# IRKitESP8266_v11.net
KiCad netlist of a schematic drawn in EAGLE
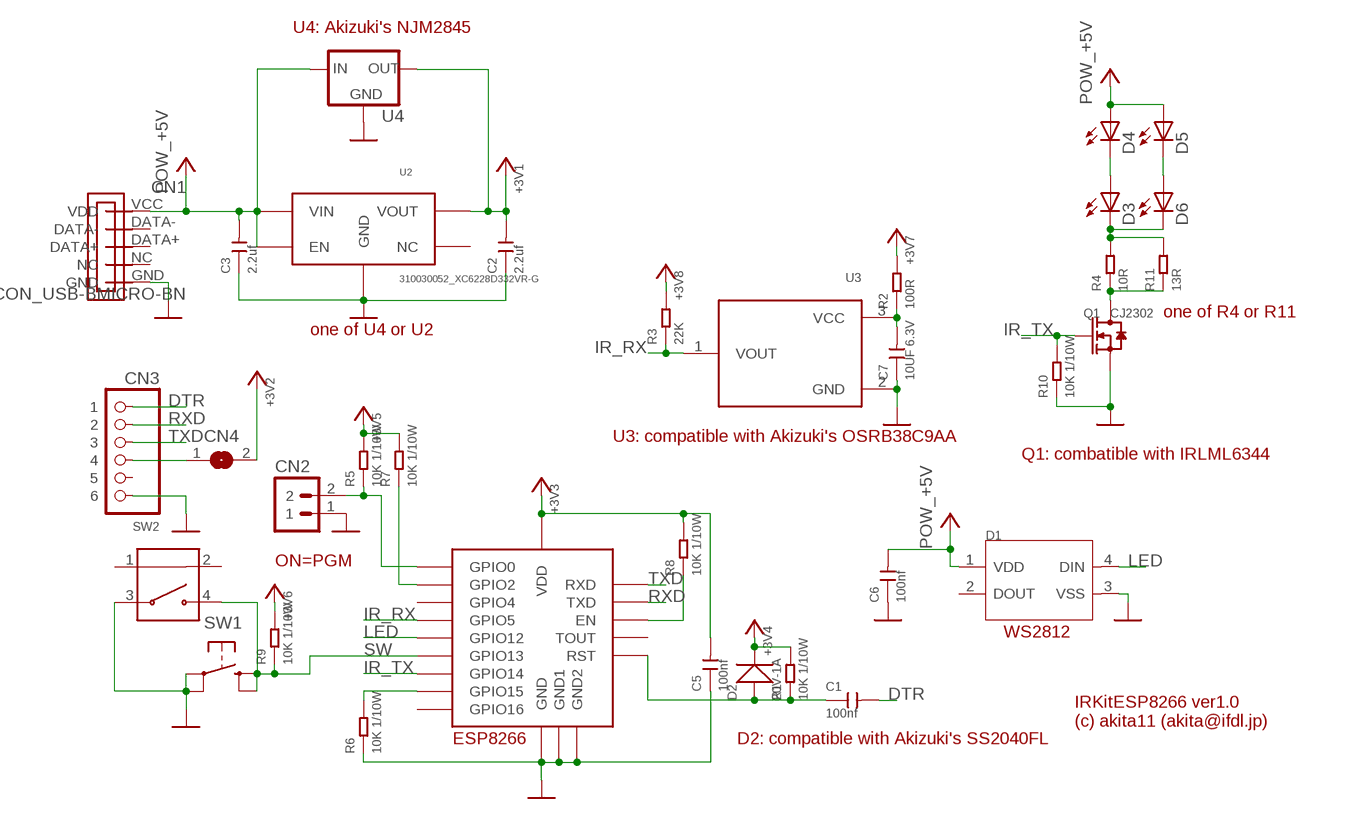
[diagram p0: schematic, sheet 1]

(export (version "E")
  (design (tool "Eeschema 10.0.6"))
  (components
    (comp (ref "C1")
      (value "100nf")
      (footprint "eagle-import:C0603")
      (fields (field (name "MPN") "CC0603KRX7R9BB104"))
      (libsource (lib "eagle-import") (part "CERAMIC-100NF-50V-10%-X7R(0603)"))
    )
    (comp (ref "C2")
      (value "2.2uf")
      (footprint "eagle-import:C0603")
      (fields (field (name "MPN") "CC0603KRX7R6BB225"))
      (libsource (lib "eagle-import") (part "CERAMIC-2.2UF-10V-10%-X7R(0603)"))
    )
    (comp (ref "C3")
      (value "2.2uf")
      (footprint "eagle-import:C0603")
      (fields (field (name "MPN") "CC0603KRX7R6BB225"))
      (libsource (lib "eagle-import") (part "CERAMIC-2.2UF-10V-10%-X7R(0603)"))
    )
    (comp (ref "C5")
      (value "100nf")
      (footprint "eagle-import:C0603")
      (fields (field (name "MPN") "CC0603KRX7R9BB104"))
      (libsource (lib "eagle-import") (part "CERAMIC-100NF-50V-10%-X7R(0603)"))
    )
    (comp (ref "C6")
      (value "100nf")
      (footprint "eagle-import:C0603")
      (fields (field (name "MPN") "CC0603KRX7R9BB104"))
      (libsource (lib "eagle-import") (part "CERAMIC-100NF-50V-10%-X7R(0603)"))
    )
    (comp (ref "C7")
      (value "10UF 6.3V")
      (footprint "eagle-import:C0603")
      (fields (field (name "MPN") "CC0603MRX5R5BB106"))
      (libsource (lib "eagle-import") (part "CERAMIC-10UF-6.3V-20%-X5R(0603)"))
    )
    (comp (ref "CN1")
      (value "CON_USB-BMICRO-BN")
      (footprint "eagle-import:MICRO-USB_B_NARROW")
      (libsource (lib "eagle-import") (part "CON_USB-BMICRO-BN"))
    )
    (comp (ref "CN2")
      (value "CON_PINHD-1X2PTH")
      (footprint "eagle-import:SPARKFUN_1X02")
      (libsource (lib "eagle-import") (part "CON_PINHD-1X2PTH"))
    )
    (comp (ref "CN3")
      (value "CON_PINHD-1X6")
      (footprint "eagle-import:1X06")
      (libsource (lib "eagle-import") (part "CON_PINHD-1X6"))
    )
    (comp (ref "CN4")
      (value "JUMPER_SJ")
      (footprint "eagle-import:JUMPER_SJ")
      (libsource (lib "eagle-import") (part "JUMPER_SJ"))
    )
    (comp (ref "D1")
      (value "SMD-RGB-LED-4P'WS2812B'")
      (footprint "eagle-import:LED4-SMD-5050")
      (libsource (lib "eagle-import") (part "SMD-RGB-LED-4P'WS2812B'"))
    )
    (comp (ref "D2")
      (value "20V-1A")
      (footprint "eagle-import:SOD-123")
      (fields (field (name "MPN") "B5819W"))
      (libsource (lib "eagle-import") (part "SMD-DIODE-SCHOTTKY-20V-1A(SOD-123)"))
    )
    (comp (ref "D3")
      (value "LED5MM")
      (footprint "eagle-import:SPARKFUN_LED5MM")
      (libsource (lib "eagle-import") (part "LED5MM"))
    )
    (comp (ref "D4")
      (value "LED5MM")
      (footprint "eagle-import:SPARKFUN_LED5MM")
      (libsource (lib "eagle-import") (part "LED5MM"))
    )
    (comp (ref "D5")
      (value "LED5MM")
      (footprint "eagle-import:SPARKFUN_LED5MM")
      (libsource (lib "eagle-import") (part "LED5MM"))
    )
    (comp (ref "D6")
      (value "LED5MM")
      (footprint "eagle-import:SPARKFUN_LED5MM")
      (libsource (lib "eagle-import") (part "LED5MM"))
    )
    (comp (ref "Q1")
      (value "CJ2302")
      (footprint "eagle-import:SOT-23")
      (libsource (lib "eagle-import") (part "SMD-MOSFET-N-CH-20V-2.1A-CJ2302(SOT-23)"))
    )
    (comp (ref "R1")
      (value "10K 1/10W")
      (footprint "eagle-import:R0603")
      (fields (field (name "MPN") "RC0603JR-0710KL"))
      (libsource (lib "eagle-import") (part "SMD-RES-10K-5%-1/10W(0603)"))
    )
    (comp (ref "R2")
      (value "100R")
      (footprint "eagle-import:R0603")
      (fields (field (name "MPN") "RC0603JR-07100RL"))
      (libsource (lib "eagle-import") (part "SMD-RES-100R-5%-1/10W(0603)"))
    )
    (comp (ref "R3")
      (value "22K")
      (footprint "eagle-import:R0603")
      (fields (field (name "MPN") "RC0603JR-0722KL"))
      (libsource (lib "eagle-import") (part "SMD-RES-22K-5%-1/10W(0603)"))
    )
    (comp (ref "R4")
      (value "10R")
      (footprint "eagle-import:R0603")
      (fields (field (name "MPN") "RC0603FR-0710RL"))
      (libsource (lib "eagle-import") (part "SMD-RES-10R-1%-1/10W(0603)"))
    )
    (comp (ref "R5")
      (value "10K 1/10W")
      (footprint "eagle-import:R0603")
      (fields (field (name "MPN") "RC0603JR-0710KL"))
      (libsource (lib "eagle-import") (part "SMD-RES-10K-5%-1/10W(0603)"))
    )
    (comp (ref "R6")
      (value "10K 1/10W")
      (footprint "eagle-import:R0603")
      (fields (field (name "MPN") "RC0603JR-0710KL"))
      (libsource (lib "eagle-import") (part "SMD-RES-10K-5%-1/10W(0603)"))
    )
    (comp (ref "R7")
      (value "10K 1/10W")
      (footprint "eagle-import:R0603")
      (fields (field (name "MPN") "RC0603JR-0710KL"))
      (libsource (lib "eagle-import") (part "SMD-RES-10K-5%-1/10W(0603)"))
    )
    (comp (ref "R8")
      (value "10K 1/10W")
      (footprint "eagle-import:R0603")
      (fields (field (name "MPN") "RC0603JR-0710KL"))
      (libsource (lib "eagle-import") (part "SMD-RES-10K-5%-1/10W(0603)"))
    )
    (comp (ref "R9")
      (value "10K 1/10W")
      (footprint "eagle-import:R0603")
      (fields (field (name "MPN") "RC0603JR-0710KL"))
      (libsource (lib "eagle-import") (part "SMD-RES-10K-5%-1/10W(0603)"))
    )
    (comp (ref "R10")
      (value "10K 1/10W")
      (footprint "eagle-import:R0603")
      (fields (field (name "MPN") "RC0603JR-0710KL"))
      (libsource (lib "eagle-import") (part "SMD-RES-10K-5%-1/10W(0603)"))
    )
    (comp (ref "R11")
      (value "13R")
      (footprint "eagle-import:R1206")
      (fields (field (name "MPN") "RC1206JR-0713RL"))
      (libsource (lib "eagle-import") (part "SMD-RES-13R-5%-1/4W(1206)"))
    )
    (comp (ref "SW1")
      (value "SW_TACTTH")
      (footprint "eagle-import:SW_B3F-10XX")
      (fields (field (name "MPN") "B3F-1000"))
      (libsource (lib "eagle-import") (part "SW_TACTTH"))
    )
    (comp (ref "SW2")
      (value "TS-1188E")
      (footprint "eagle-import:TS-1188E")
      (libsource (lib "eagle-import") (part "TS-1188E"))
    )
    (comp (ref "U1")
      (value "MOD_ESP8266WROOM02")
      (footprint "eagle-import:MOD_ESP8266WROOM02")
      (libsource (lib "eagle-import") (part "MOD_ESP8266WROOM02"))
    )
    (comp (ref "U2")
      (value "310030052_XC6228D332VR-G")
      (footprint "eagle-import:SOT25J")
      (libsource (lib "eagle-import") (part "310030052_XC6228D332VR-G"))
    )
    (comp (ref "U3")
      (value "TSOP382")
      (footprint "eagle-import:TSOP382")
      (libsource (lib "eagle-import") (part "TSOP382"))
    )
    (comp (ref "U4")
      (value "REG_78XXTO252-3")
      (footprint "eagle-import:TO-252-3")
      (libsource (lib "eagle-import") (part "REG_78XXTO252-3"))
    )
  )
  (nets
    (net (code "1") (name "/DTR") (class "Default")
      (node (ref "C1") (pin "2") (pinfunction "2_2") (pintype "passive"))
      (node (ref "CN3") (pin "1") (pinfunction "1_1") (pintype "passive"))
    )
    (net (code "2") (name "/IR_RX") (class "Default")
      (node (ref "R3") (pin "1") (pinfunction "1_1") (pintype "passive"))
      (node (ref "U1") (pin "P$14") (pinfunction "GPIO5_P$14") (pintype "bidirectional"))
      (node (ref "U3") (pin "1") (pinfunction "VOUT_1") (pintype "bidirectional"))
    )
    (net (code "3") (name "/IR_TX") (class "Default")
      (node (ref "Q1") (pin "1") (pinfunction "G_1") (pintype "passive"))
      (node (ref "R10") (pin "2") (pinfunction "2_2") (pintype "passive"))
      (node (ref "U1") (pin "P$3") (pinfunction "GPIO14_P$3") (pintype "bidirectional"))
    )
    (net (code "4") (name "/LED") (class "Default")
      (node (ref "D1") (pin "4") (pinfunction "DIN_4") (pintype "bidirectional"))
      (node (ref "U1") (pin "P$4") (pinfunction "GPIO12_P$4") (pintype "bidirectional"))
    )
    (net (code "5") (name "/RXD") (class "Default")
      (node (ref "CN3") (pin "2") (pinfunction "2_2") (pintype "passive"))
      (node (ref "U1") (pin "P$12") (pinfunction "TXD_P$12") (pintype "bidirectional"))
    )
    (net (code "6") (name "/SW") (class "Default")
      (node (ref "R9") (pin "1") (pinfunction "1_1") (pintype "passive"))
      (node (ref "SW1") (pin "1") (pinfunction "S_1") (pintype "passive"))
      (node (ref "SW1") (pin "2") (pinfunction "S1_2") (pintype "passive"))
      (node (ref "SW2") (pin "4") (pinfunction "4_4") (pintype "bidirectional"))
      (node (ref "U1") (pin "P$5") (pinfunction "GPIO13_P$5") (pintype "bidirectional"))
    )
    (net (code "7") (name "/TXD") (class "Default")
      (node (ref "CN3") (pin "3") (pinfunction "3_3") (pintype "passive"))
      (node (ref "U1") (pin "P$11") (pinfunction "RXD_P$11") (pintype "bidirectional"))
    )
    (net (code "8") (name "Net-(CN3-Pad4)") (class "Default")
      (node (ref "CN3") (pin "4") (pinfunction "4_4") (pintype "passive"))
      (node (ref "CN4") (pin "1") (pinfunction "1_1") (pintype "passive"))
    )
    (net (code "9") (name "Net-(D3-C)") (class "Default")
      (node (ref "D3") (pin "K") (pinfunction "C_K") (pintype "passive"))
      (node (ref "D6") (pin "K") (pinfunction "C_K") (pintype "passive"))
      (node (ref "R11") (pin "2") (pinfunction "2_2") (pintype "passive"))
      (node (ref "R4") (pin "2") (pinfunction "2_2") (pintype "passive"))
    )
    (net (code "10") (name "Net-(D4-C)") (class "Default")
      (node (ref "D3") (pin "A") (pinfunction "A_A") (pintype "passive"))
      (node (ref "D4") (pin "K") (pinfunction "C_K") (pintype "passive"))
    )
    (net (code "11") (name "Net-(D5-C)") (class "Default")
      (node (ref "D5") (pin "K") (pinfunction "C_K") (pintype "passive"))
      (node (ref "D6") (pin "A") (pinfunction "A_A") (pintype "passive"))
    )
    (net (code "12") (name "Net-(Q1-D)") (class "Default")
      (node (ref "Q1") (pin "3") (pinfunction "D_3") (pintype "passive"))
      (node (ref "R11") (pin "1") (pinfunction "1_1") (pintype "passive"))
      (node (ref "R4") (pin "1") (pinfunction "1_1") (pintype "passive"))
    )
    (net (code "13") (name "Net-(U1-EN)") (class "Default")
      (node (ref "R8") (pin "1") (pinfunction "1_1") (pintype "passive"))
      (node (ref "U1") (pin "P$2") (pinfunction "EN_P$2") (pintype "bidirectional"))
    )
    (net (code "14") (name "Net-(U1-GPIO0)") (class "Default")
      (node (ref "CN2") (pin "2") (pinfunction "2_2") (pintype "passive"))
      (node (ref "R5") (pin "1") (pinfunction "1_1") (pintype "passive"))
      (node (ref "U1") (pin "P$8") (pinfunction "GPIO0_P$8") (pintype "bidirectional"))
    )
    (net (code "15") (name "Net-(U1-GPIO2)") (class "Default")
      (node (ref "R7") (pin "1") (pinfunction "1_1") (pintype "passive"))
      (node (ref "U1") (pin "P$7") (pinfunction "GPIO2_P$7") (pintype "bidirectional"))
    )
    (net (code "16") (name "Net-(U1-GPIO15)") (class "Default")
      (node (ref "R6") (pin "2") (pinfunction "2_2") (pintype "passive"))
      (node (ref "U1") (pin "P$6") (pinfunction "GPIO15_P$6") (pintype "bidirectional"))
    )
    (net (code "17") (name "Net-(U1-RST)") (class "Default")
      (node (ref "C1") (pin "1") (pinfunction "1_1") (pintype "passive"))
      (node (ref "D2") (pin "+") (pinfunction "+_+") (pintype "passive"))
      (node (ref "R1") (pin "1") (pinfunction "1_1") (pintype "passive"))
      (node (ref "U1") (pin "P$15") (pinfunction "RST_P$15") (pintype "bidirectional"))
    )
    (net (code "18") (name "Net-(U3-VCC)") (class "Default")
      (node (ref "C7") (pin "2") (pinfunction "2_2") (pintype "passive"))
      (node (ref "R2") (pin "1") (pinfunction "1_1") (pintype "passive"))
      (node (ref "U3") (pin "3") (pinfunction "VCC_3") (pintype "bidirectional"))
    )
    (net (code "19") (name "POW_+3V3") (class "Default")
      (node (ref "C2") (pin "2") (pinfunction "2_2") (pintype "passive"))
      (node (ref "C5") (pin "2") (pinfunction "2_2") (pintype "passive"))
      (node (ref "CN4") (pin "2") (pinfunction "2_2") (pintype "passive"))
      (node (ref "D2") (pin "-") (pinfunction "-_-") (pintype "passive"))
      (node (ref "R1") (pin "2") (pinfunction "2_2") (pintype "passive"))
      (node (ref "R2") (pin "2") (pinfunction "2_2") (pintype "passive"))
      (node (ref "R3") (pin "2") (pinfunction "2_2") (pintype "passive"))
      (node (ref "R5") (pin "2") (pinfunction "2_2") (pintype "passive"))
      (node (ref "R7") (pin "2") (pinfunction "2_2") (pintype "passive"))
      (node (ref "R8") (pin "2") (pinfunction "2_2") (pintype "passive"))
      (node (ref "R9") (pin "2") (pinfunction "2_2") (pintype "passive"))
      (node (ref "U1") (pin "P$1") (pinfunction "VDD_P$1") (pintype "bidirectional"))
      (node (ref "U2") (pin "P$5") (pinfunction "VOUT_P$5") (pintype "bidirectional"))
      (node (ref "U4") (pin "P$3") (pinfunction "OUT_P$3") (pintype "output"))
    )
    (net (code "20") (name "POW_+5V") (class "Default")
      (node (ref "C3") (pin "2") (pinfunction "2_2") (pintype "passive"))
      (node (ref "C6") (pin "2") (pinfunction "2_2") (pintype "passive"))
      (node (ref "CN1") (pin "VCC") (pinfunction "VDD_VCC") (pintype "power_in"))
      (node (ref "D1") (pin "1") (pinfunction "VDD_1") (pintype "bidirectional"))
      (node (ref "D4") (pin "A") (pinfunction "A_A") (pintype "passive"))
      (node (ref "D5") (pin "A") (pinfunction "A_A") (pintype "passive"))
      (node (ref "U2") (pin "P$1") (pinfunction "VIN_P$1") (pintype "bidirectional"))
      (node (ref "U2") (pin "P$3") (pinfunction "EN_P$3") (pintype "bidirectional"))
      (node (ref "U4") (pin "P$1") (pinfunction "IN_P$1") (pintype "input"))
    )
    (net (code "21") (name "POW_GND") (class "Default")
      (node (ref "C2") (pin "1") (pinfunction "1_1") (pintype "passive"))
      (node (ref "C3") (pin "1") (pinfunction "1_1") (pintype "passive"))
      (node (ref "C5") (pin "1") (pinfunction "1_1") (pintype "passive"))
      (node (ref "C6") (pin "1") (pinfunction "1_1") (pintype "passive"))
      (node (ref "C7") (pin "1") (pinfunction "1_1") (pintype "passive"))
      (node (ref "CN1") (pin "GND") (pinfunction "GND_GND") (pintype "power_in"))
      (node (ref "CN2") (pin "1") (pinfunction "1_1") (pintype "passive"))
      (node (ref "CN3") (pin "6") (pinfunction "6_6") (pintype "passive"))
      (node (ref "D1") (pin "3") (pinfunction "VSS_3") (pintype "bidirectional"))
      (node (ref "Q1") (pin "2") (pinfunction "S_2") (pintype "passive"))
      (node (ref "R10") (pin "1") (pinfunction "1_1") (pintype "passive"))
      (node (ref "R6") (pin "1") (pinfunction "1_1") (pintype "passive"))
      (node (ref "SW1") (pin "3") (pinfunction "P_3") (pintype "passive"))
      (node (ref "SW1") (pin "4") (pinfunction "P1_4") (pintype "passive"))
      (node (ref "SW2") (pin "3") (pinfunction "3_3") (pintype "bidirectional"))
      (node (ref "U1") (pin "P$13") (pinfunction "GND1_P$13") (pintype "bidirectional"))
      (node (ref "U1") (pin "P$18") (pinfunction "GND2_P$18") (pintype "bidirectional"))
      (node (ref "U1") (pin "P$9") (pinfunction "GND_P$9") (pintype "bidirectional"))
      (node (ref "U2") (pin "P$2") (pinfunction "GND_P$2") (pintype "bidirectional"))
      (node (ref "U3") (pin "2") (pinfunction "GND_2") (pintype "bidirectional"))
      (node (ref "U4") (pin "P$2") (pinfunction "GND_P$2") (pintype "input"))
    )
    (net (code "22") (name "unconnected-(CN1-PadDATA+)") (class "Default")
      (node (ref "CN1") (pin "DATA+") (pinfunction "DATA+_DATA+") (pintype "bidirectional"))
    )
    (net (code "23") (name "unconnected-(CN1-PadDATA-)") (class "Default")
      (node (ref "CN1") (pin "DATA-") (pinfunction "DATA-_DATA-") (pintype "bidirectional"))
    )
    (net (code "24") (name "unconnected-(CN1-PadNC)") (class "Default")
      (node (ref "CN1") (pin "NC") (pinfunction "NC_NC") (pintype "bidirectional"))
    )
    (net (code "25") (name "unconnected-(CN3-Pad5)") (class "Default")
      (node (ref "CN3") (pin "5") (pinfunction "5_5") (pintype "passive"))
    )
    (net (code "26") (name "unconnected-(D1-DOUT-Pad2)") (class "Default")
      (node (ref "D1") (pin "2") (pinfunction "DOUT_2") (pintype "bidirectional"))
    )
    (net (code "27") (name "unconnected-(SW2-Pad1)") (class "Default")
      (node (ref "SW2") (pin "1") (pinfunction "1_1") (pintype "bidirectional"))
    )
    (net (code "28") (name "unconnected-(SW2-Pad2)") (class "Default")
      (node (ref "SW2") (pin "2") (pinfunction "2_2") (pintype "bidirectional"))
    )
    (net (code "29") (name "unconnected-(U1-GPIO4-PadP$10)") (class "Default")
      (node (ref "U1") (pin "P$10") (pinfunction "GPIO4_P$10") (pintype "bidirectional"))
    )
    (net (code "30") (name "unconnected-(U1-GPIO16-PadP$17)") (class "Default")
      (node (ref "U1") (pin "P$17") (pinfunction "GPIO16_P$17") (pintype "bidirectional"))
    )
    (net (code "31") (name "unconnected-(U1-TOUT-PadP$16)") (class "Default")
      (node (ref "U1") (pin "P$16") (pinfunction "TOUT_P$16") (pintype "bidirectional"))
    )
    (net (code "32") (name "unconnected-(U2-NC-PadP$4)") (class "Default")
      (node (ref "U2") (pin "P$4") (pinfunction "NC_P$4") (pintype "bidirectional"))
    )
  )
)
